# source_eagle.net
KiCad netlist of a schematic drawn in EAGLE
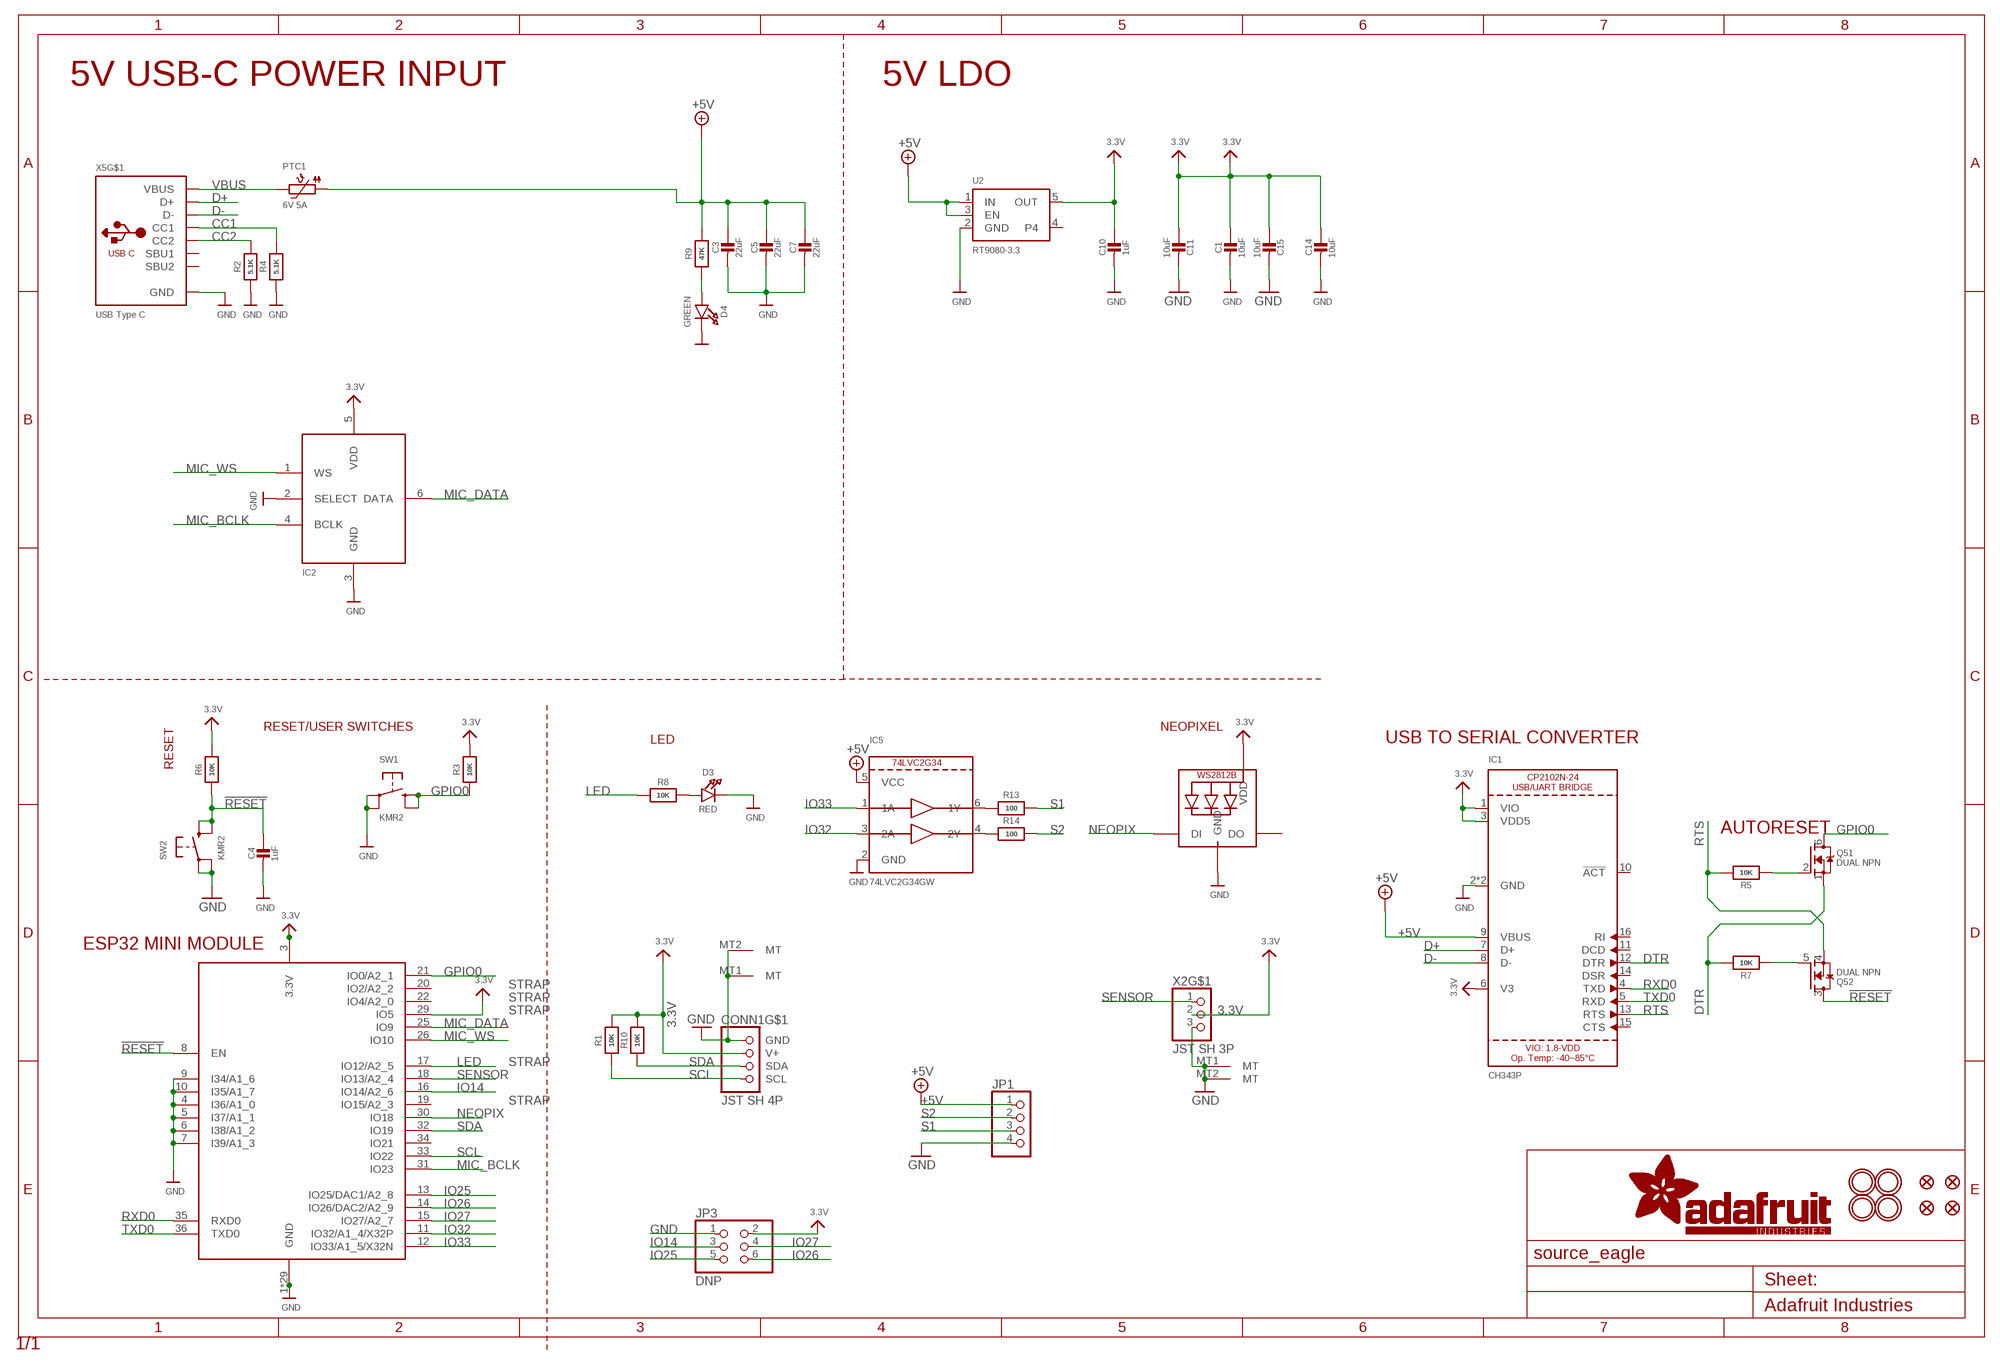
[diagram p0: schematic, sheet 1]

(export (version "E")
  (design (tool "Eeschema 10.0.6"))
  (components
    (comp (ref "C1")
      (value "10uF")
      (footprint "eagle-import:0805-NO")
      (libsource (lib "eagle-import") (part "CAP_CERAMIC0805-NOOUTLINE"))
    )
    (comp (ref "C3")
      (value "22uF")
      (footprint "eagle-import:0805-NO")
      (libsource (lib "eagle-import") (part "CAP_CERAMIC0805-NOOUTLINE"))
    )
    (comp (ref "C4")
      (value "1uF")
      (footprint "eagle-import:_0402NO")
      (libsource (lib "eagle-import") (part "CAP_CERAMIC_0402NO"))
    )
    (comp (ref "C5")
      (value "22uF")
      (footprint "eagle-import:0805-NO")
      (libsource (lib "eagle-import") (part "CAP_CERAMIC0805-NOOUTLINE"))
    )
    (comp (ref "C7")
      (value "22uF")
      (footprint "eagle-import:0805-NO")
      (libsource (lib "eagle-import") (part "CAP_CERAMIC0805-NOOUTLINE"))
    )
    (comp (ref "C10")
      (value "1uF")
      (footprint "eagle-import:_0402NO")
      (libsource (lib "eagle-import") (part "CAP_CERAMIC_0402NO"))
    )
    (comp (ref "C11")
      (value "10uF")
      (footprint "eagle-import:0805-NO")
      (libsource (lib "eagle-import") (part "CAP_CERAMIC0805-NOOUTLINE"))
    )
    (comp (ref "C14")
      (value "10uF")
      (footprint "eagle-import:0805-NO")
      (libsource (lib "eagle-import") (part "CAP_CERAMIC0805-NOOUTLINE"))
    )
    (comp (ref "C15")
      (value "10uF")
      (footprint "eagle-import:0805-NO")
      (libsource (lib "eagle-import") (part "CAP_CERAMIC0805-NOOUTLINE"))
    )
    (comp (ref "CONN1")
      (value "JST SH 4P")
      (footprint "eagle-import:JST_SH4")
      (libsource (lib "eagle-import") (part "STEMMA_I2C_QT"))
    )
    (comp (ref "D3")
      (value "RED")
      (footprint "eagle-import:CHIPLED_0603_NOOUTLINE")
      (libsource (lib "eagle-import") (part "LED0603_NOOUTLINE"))
    )
    (comp (ref "D4")
      (value "GREEN")
      (footprint "eagle-import:CHIPLED_0603_NOOUTLINE")
      (libsource (lib "eagle-import") (part "LED0603_NOOUTLINE"))
    )
    (comp (ref "IC1")
      (value "CH343P")
      (footprint "eagle-import:QFN16_3MM")
      (libsource (lib "eagle-import") (part "CH343P"))
    )
    (comp (ref "IC2")
      (value "ICS-43434")
      (footprint "eagle-import:SPH0645LM4H")
      (libsource (lib "eagle-import") (part "MIC_I2S_SPH0645"))
    )
    (comp (ref "IC5")
      (value "74LVC2G34GW")
      (footprint "eagle-import:SC70-6L")
      (libsource (lib "eagle-import") (part "74LVC2G34GW"))
    )
    (comp (ref "JP1")
      (value "HEADER-1X4")
      (footprint "eagle-import:1X04_OVAL")
      (libsource (lib "eagle-import") (part "HEADER-1X4"))
    )
    (comp (ref "JP3")
      (value "DNP")
      (footprint "eagle-import:2X03_ROUND_70MIL")
      (libsource (lib "eagle-import") (part "HEADER-2X3"))
    )
    (comp (ref "LED1")
      (value "WS2812B_SK6805_1515")
      (footprint "eagle-import:SK6805_1515")
      (libsource (lib "eagle-import") (part "WS2812B_SK6805_1515"))
    )
    (comp (ref "PTC1")
      (value "6V 5A")
      (footprint "eagle-import:PTC1210")
      (libsource (lib "eagle-import") (part "PTC1210"))
    )
    (comp (ref "Q5")
      (value "DUAL NPN")
      (footprint "eagle-import:SOT363")
      (fields (field (name "JLC_ROTATION") "90"))
      (libsource (lib "eagle-import") (part "MOSFET-N_DUAL"))
    )
    (comp (ref "R1")
      (value "10K")
      (footprint "eagle-import:_0402NO")
      (libsource (lib "eagle-import") (part "RESISTOR_0402NO"))
    )
    (comp (ref "R2")
      (value "5.1K")
      (footprint "eagle-import:_0402NO")
      (libsource (lib "eagle-import") (part "RESISTOR_0402NO"))
    )
    (comp (ref "R3")
      (value "10K")
      (footprint "eagle-import:_0402NO")
      (libsource (lib "eagle-import") (part "RESISTOR_0402NO"))
    )
    (comp (ref "R4")
      (value "5.1K")
      (footprint "eagle-import:_0402NO")
      (libsource (lib "eagle-import") (part "RESISTOR_0402NO"))
    )
    (comp (ref "R5")
      (value "10K")
      (footprint "eagle-import:_0402NO")
      (libsource (lib "eagle-import") (part "RESISTOR_0402NO"))
    )
    (comp (ref "R6")
      (value "10K")
      (footprint "eagle-import:_0402NO")
      (libsource (lib "eagle-import") (part "RESISTOR_0402NO"))
    )
    (comp (ref "R7")
      (value "10K")
      (footprint "eagle-import:_0402NO")
      (libsource (lib "eagle-import") (part "RESISTOR_0402NO"))
    )
    (comp (ref "R8")
      (value "10K")
      (footprint "eagle-import:_0402NO")
      (libsource (lib "eagle-import") (part "RESISTOR_0402NO"))
    )
    (comp (ref "R9")
      (value "47K")
      (footprint "eagle-import:_0402NO")
      (libsource (lib "eagle-import") (part "RESISTOR_0402NO"))
    )
    (comp (ref "R10")
      (value "10K")
      (footprint "eagle-import:_0402NO")
      (libsource (lib "eagle-import") (part "RESISTOR_0402NO"))
    )
    (comp (ref "R13")
      (value "100")
      (footprint "eagle-import:_0402NO")
      (libsource (lib "eagle-import") (part "RESISTOR_0402NO"))
    )
    (comp (ref "R14")
      (value "100")
      (footprint "eagle-import:_0402NO")
      (libsource (lib "eagle-import") (part "RESISTOR_0402NO"))
    )
    (comp (ref "SW1")
      (value "KMR2")
      (footprint "eagle-import:BTN_RKB2_4.6X2.8")
      (libsource (lib "eagle-import") (part "SWITCH_TACT_SMT_RKB2"))
    )
    (comp (ref "SW2")
      (value "KMR2")
      (footprint "eagle-import:BTN_RKB2_4.6X2.8")
      (libsource (lib "eagle-import") (part "SWITCH_TACT_SMT_RKB2"))
    )
    (comp (ref "U$14")
      (value "MOUNTINGHOLE2.5")
      (footprint "eagle-import:MOUNTINGHOLE_2.5_PLATED")
      (libsource (lib "eagle-import") (part "MOUNTINGHOLE2.5"))
    )
    (comp (ref "U$20")
      (value "MOUNTINGHOLE2.5")
      (footprint "eagle-import:MOUNTINGHOLE_2.5_PLATED")
      (libsource (lib "eagle-import") (part "MOUNTINGHOLE2.5"))
    )
    (comp (ref "U$23")
      (value "FIDUCIAL_0.5MM")
      (footprint "eagle-import:FIDUCIAL_0.5MM")
      (libsource (lib "eagle-import") (part "FIDUCIAL_0.5MM"))
    )
    (comp (ref "U$25")
      (value "FIDUCIAL_0.5MM")
      (footprint "eagle-import:FIDUCIAL_0.5MM")
      (libsource (lib "eagle-import") (part "FIDUCIAL_0.5MM"))
    )
    (comp (ref "U$28")
      (value "MOUNTINGHOLE2.5")
      (footprint "eagle-import:MOUNTINGHOLE_2.5_PLATED")
      (libsource (lib "eagle-import") (part "MOUNTINGHOLE2.5"))
    )
    (comp (ref "U$31")
      (value "MOUNTINGHOLE2.5")
      (footprint "eagle-import:MOUNTINGHOLE_2.5_PLATED")
      (libsource (lib "eagle-import") (part "MOUNTINGHOLE2.5"))
    )
    (comp (ref "U$34")
      (value "FIDUCIAL_0.5MM")
      (footprint "eagle-import:FIDUCIAL_0.5MM")
      (libsource (lib "eagle-import") (part "FIDUCIAL_0.5MM"))
    )
    (comp (ref "U$35")
      (value "FIDUCIAL_0.5MM")
      (footprint "eagle-import:FIDUCIAL_0.5MM")
      (libsource (lib "eagle-import") (part "FIDUCIAL_0.5MM"))
    )
    (comp (ref "U2")
      (value "RT9080-3.3")
      (footprint "eagle-import:SOT23-5")
      (fields (field (name "JLC_ROTATION") "0"))
      (libsource (lib "eagle-import") (part "VREG_SOT23-5"))
    )
    (comp (ref "X2")
      (value "JST SH 3P")
      (footprint "eagle-import:JST_SH3")
      (libsource (lib "eagle-import") (part "CON_JST_SH_3PINHORZ"))
    )
    (comp (ref "X4")
      (value "ESP32-MINI-1")
      (footprint "eagle-import:ESP32-MINI-1")
      (libsource (lib "eagle-import") (part "ESP32-MINI-1"))
    )
    (comp (ref "X5")
      (value "USB Type C")
      (footprint "eagle-import:USB_C_CUSB31-CFM2AX-01-X")
      (libsource (lib "eagle-import") (part "USB_C"))
    )
  )
  (nets
    (net (code "1") (name "+5V") (class "Default")
      (node (ref "C3") (pin "1") (pinfunction "1_1") (pintype "passive"))
      (node (ref "C5") (pin "1") (pinfunction "1_1") (pintype "passive"))
      (node (ref "C7") (pin "1") (pinfunction "1_1") (pintype "passive"))
      (node (ref "IC1") (pin "9") (pinfunction "VBUS_9") (pintype "power_in"))
      (node (ref "IC5") (pin "5") (pinfunction "VCC_5") (pintype "power_in"))
      (node (ref "JP1") (pin "1") (pinfunction "1_1") (pintype "passive"))
      (node (ref "PTC1") (pin "P$1") (pinfunction "1_P$1") (pintype "passive"))
      (node (ref "R9") (pin "2") (pinfunction "2_2") (pintype "passive"))
      (node (ref "U2") (pin "1") (pinfunction "IN_1") (pintype "power_in"))
      (node (ref "U2") (pin "3") (pinfunction "EN_3") (pintype "input"))
    )
    (net (code "2") (name "/CC1") (class "Default")
      (node (ref "R4") (pin "2") (pinfunction "2_2") (pintype "passive"))
      (node (ref "X5") (pin "A5") (pinfunction "CC1_A5") (pintype "bidirectional"))
    )
    (net (code "3") (name "/CC2") (class "Default")
      (node (ref "R2") (pin "2") (pinfunction "2_2") (pintype "passive"))
      (node (ref "X5") (pin "B5") (pinfunction "CC2_B5") (pintype "bidirectional"))
    )
    (net (code "4") (name "/D+") (class "Default")
      (node (ref "IC1") (pin "7") (pinfunction "D+_7") (pintype "bidirectional"))
      (node (ref "X5") (pin "A6") (pinfunction "D+_A6") (pintype "bidirectional"))
      (node (ref "X5") (pin "B6") (pinfunction "D+_B6") (pintype "bidirectional"))
    )
    (net (code "5") (name "/D-") (class "Default")
      (node (ref "IC1") (pin "8") (pinfunction "D-_8") (pintype "bidirectional"))
      (node (ref "X5") (pin "A7") (pinfunction "D-_A7") (pintype "bidirectional"))
      (node (ref "X5") (pin "B7") (pinfunction "D-_B7") (pintype "bidirectional"))
    )
    (net (code "6") (name "/DTR") (class "Default")
      (node (ref "IC1") (pin "12") (pinfunction "DTR_12") (pintype "output"))
      (node (ref "Q5") (pin "1") (pinfunction "S_1") (pintype "bidirectional"))
      (node (ref "R7") (pin "2") (pinfunction "2_2") (pintype "passive"))
    )
    (net (code "7") (name "/GPIO0") (class "Default")
      (node (ref "Q5") (pin "6") (pinfunction "D_6") (pintype "bidirectional"))
      (node (ref "R3") (pin "1") (pinfunction "1_1") (pintype "passive"))
      (node (ref "SW1") (pin "B") (pinfunction "S_B") (pintype "passive"))
      (node (ref "SW1") (pin "B'") (pinfunction "S1_B'") (pintype "passive"))
      (node (ref "X4") (pin "21") (pinfunction "IO0/A2_1_21") (pintype "bidirectional"))
    )
    (net (code "8") (name "/IO14") (class "Default")
      (node (ref "JP3") (pin "3") (pinfunction "3_3") (pintype "passive"))
      (node (ref "X4") (pin "16") (pinfunction "IO14/A2_6_16") (pintype "bidirectional"))
    )
    (net (code "9") (name "/IO25") (class "Default")
      (node (ref "JP3") (pin "5") (pinfunction "5_5") (pintype "passive"))
      (node (ref "X4") (pin "13") (pinfunction "IO25/DAC1/A2_8_13") (pintype "bidirectional"))
    )
    (net (code "10") (name "/IO26") (class "Default")
      (node (ref "JP3") (pin "6") (pinfunction "6_6") (pintype "passive"))
      (node (ref "X4") (pin "14") (pinfunction "IO26/DAC2/A2_9_14") (pintype "bidirectional"))
    )
    (net (code "11") (name "/IO27") (class "Default")
      (node (ref "JP3") (pin "4") (pinfunction "4_4") (pintype "passive"))
      (node (ref "X4") (pin "15") (pinfunction "IO27/A2_7_15") (pintype "bidirectional"))
    )
    (net (code "12") (name "/IO32") (class "Default")
      (node (ref "IC5") (pin "3") (pinfunction "2A_3") (pintype "input"))
      (node (ref "X4") (pin "11") (pinfunction "IO32/A1_4/X32P_11") (pintype "bidirectional"))
    )
    (net (code "13") (name "/IO33") (class "Default")
      (node (ref "IC5") (pin "1") (pinfunction "1A_1") (pintype "input"))
      (node (ref "X4") (pin "12") (pinfunction "IO33/A1_5/X32N_12") (pintype "bidirectional"))
    )
    (net (code "14") (name "/LED") (class "Default")
      (node (ref "R8") (pin "1") (pinfunction "1_1") (pintype "passive"))
      (node (ref "X4") (pin "17") (pinfunction "IO12/A2_5_17") (pintype "bidirectional"))
    )
    (net (code "15") (name "/MIC_BCLK") (class "Default")
      (node (ref "IC2") (pin "4") (pinfunction "BCLK_4") (pintype "input"))
      (node (ref "X4") (pin "31") (pinfunction "IO23_31") (pintype "bidirectional"))
    )
    (net (code "16") (name "/MIC_DATA") (class "Default")
      (node (ref "IC2") (pin "6") (pinfunction "DATA_6") (pintype "output"))
      (node (ref "X4") (pin "25") (pinfunction "IO9_25") (pintype "bidirectional"))
    )
    (net (code "17") (name "/MIC_WS") (class "Default")
      (node (ref "IC2") (pin "1") (pinfunction "WS_1") (pintype "input"))
      (node (ref "X4") (pin "26") (pinfunction "IO10_26") (pintype "bidirectional"))
    )
    (net (code "18") (name "/NEOPIX") (class "Default")
      (node (ref "LED1") (pin "1") (pinfunction "DI_1") (pintype "input"))
      (node (ref "X4") (pin "30") (pinfunction "IO18_30") (pintype "bidirectional"))
    )
    (net (code "19") (name "/RTS") (class "Default")
      (node (ref "IC1") (pin "13") (pinfunction "RTS_13") (pintype "output"))
      (node (ref "Q5") (pin "4") (pinfunction "S_4") (pintype "bidirectional"))
      (node (ref "R5") (pin "2") (pinfunction "2_2") (pintype "passive"))
    )
    (net (code "20") (name "/RXD0") (class "Default")
      (node (ref "IC1") (pin "4") (pinfunction "TXD_4") (pintype "output"))
      (node (ref "X4") (pin "35") (pinfunction "RXD0_35") (pintype "input"))
    )
    (net (code "21") (name "/S1") (class "Default")
      (node (ref "JP1") (pin "3") (pinfunction "3_3") (pintype "passive"))
      (node (ref "R13") (pin "2") (pinfunction "2_2") (pintype "passive"))
    )
    (net (code "22") (name "/S2") (class "Default")
      (node (ref "JP1") (pin "2") (pinfunction "2_2") (pintype "passive"))
      (node (ref "R14") (pin "2") (pinfunction "2_2") (pintype "passive"))
    )
    (net (code "23") (name "/SCL") (class "Default")
      (node (ref "CONN1") (pin "4") (pinfunction "SCL_4") (pintype "passive"))
      (node (ref "R1") (pin "1") (pinfunction "1_1") (pintype "passive"))
      (node (ref "X4") (pin "33") (pinfunction "IO22_33") (pintype "bidirectional"))
    )
    (net (code "24") (name "/SDA") (class "Default")
      (node (ref "CONN1") (pin "3") (pinfunction "SDA_3") (pintype "passive"))
      (node (ref "R10") (pin "1") (pinfunction "1_1") (pintype "passive"))
      (node (ref "X4") (pin "32") (pinfunction "IO19_32") (pintype "bidirectional"))
    )
    (net (code "25") (name "/SENSOR") (class "Default")
      (node (ref "X2") (pin "1") (pinfunction "1_1") (pintype "passive"))
      (node (ref "X4") (pin "18") (pinfunction "IO13/A2_4_18") (pintype "bidirectional"))
    )
    (net (code "26") (name "/TXD0") (class "Default")
      (node (ref "IC1") (pin "5") (pinfunction "RXD_5") (pintype "input"))
      (node (ref "X4") (pin "36") (pinfunction "TXD0_36") (pintype "output"))
    )
    (net (code "27") (name "/VBUS") (class "Default")
      (node (ref "PTC1") (pin "P$2") (pinfunction "2_P$2") (pintype "passive"))
      (node (ref "X5") (pin "A4B9") (pinfunction "VBUS_A4B9") (pintype "power_in"))
      (node (ref "X5") (pin "B4A9") (pinfunction "VBUS_B4A9") (pintype "power_in"))
    )
    (net (code "28") (name "/~{RESET}") (class "Default")
      (node (ref "C4") (pin "1") (pinfunction "1_1") (pintype "passive"))
      (node (ref "Q5") (pin "3") (pinfunction "D_3") (pintype "bidirectional"))
      (node (ref "R6") (pin "1") (pinfunction "1_1") (pintype "passive"))
      (node (ref "SW2") (pin "B") (pinfunction "S_B") (pintype "passive"))
      (node (ref "SW2") (pin "B'") (pinfunction "S1_B'") (pintype "passive"))
      (node (ref "X4") (pin "8") (pinfunction "EN_8") (pintype "input"))
    )
    (net (code "29") (name "3.3V") (class "Default")
      (node (ref "C1") (pin "1") (pinfunction "1_1") (pintype "passive"))
      (node (ref "C10") (pin "1") (pinfunction "1_1") (pintype "passive"))
      (node (ref "C11") (pin "1") (pinfunction "1_1") (pintype "passive"))
      (node (ref "C14") (pin "1") (pinfunction "1_1") (pintype "passive"))
      (node (ref "C15") (pin "1") (pinfunction "1_1") (pintype "passive"))
      (node (ref "CONN1") (pin "2") (pinfunction "V+_2") (pintype "passive"))
      (node (ref "IC1") (pin "1") (pinfunction "VIO_1") (pintype "power_in"))
      (node (ref "IC1") (pin "3") (pinfunction "VDD5_3") (pintype "power_in"))
      (node (ref "IC1") (pin "6") (pinfunction "V3_6") (pintype "passive"))
      (node (ref "IC2") (pin "5") (pinfunction "VDD_5") (pintype "power_in"))
      (node (ref "JP3") (pin "2") (pinfunction "2_2") (pintype "passive"))
      (node (ref "LED1") (pin "2") (pinfunction "VDD_2") (pintype "power_in"))
      (node (ref "R1") (pin "2") (pinfunction "2_2") (pintype "passive"))
      (node (ref "R10") (pin "2") (pinfunction "2_2") (pintype "passive"))
      (node (ref "R3") (pin "2") (pinfunction "2_2") (pintype "passive"))
      (node (ref "R6") (pin "2") (pinfunction "2_2") (pintype "passive"))
      (node (ref "U2") (pin "5") (pinfunction "OUT_5") (pintype "power_in"))
      (node (ref "X2") (pin "2") (pinfunction "2_2") (pintype "passive"))
      (node (ref "X4") (pin "29") (pinfunction "IO5_29") (pintype "bidirectional"))
      (node (ref "X4") (pin "3") (pinfunction "3.3V_3") (pintype "passive"))
    )
    (net (code "30") (name "GND") (class "Default")
      (node (ref "C1") (pin "2") (pinfunction "2_2") (pintype "passive"))
      (node (ref "C10") (pin "2") (pinfunction "2_2") (pintype "passive"))
      (node (ref "C11") (pin "2") (pinfunction "2_2") (pintype "passive"))
      (node (ref "C14") (pin "2") (pinfunction "2_2") (pintype "passive"))
      (node (ref "C15") (pin "2") (pinfunction "2_2") (pintype "passive"))
      (node (ref "C3") (pin "2") (pinfunction "2_2") (pintype "passive"))
      (node (ref "C4") (pin "2") (pinfunction "2_2") (pintype "passive"))
      (node (ref "C5") (pin "2") (pinfunction "2_2") (pintype "passive"))
      (node (ref "C7") (pin "2") (pinfunction "2_2") (pintype "passive"))
      (node (ref "CONN1") (pin "1") (pinfunction "GND_1") (pintype "passive"))
      (node (ref "CONN1") (pin "MT1") (pinfunction "MT_MT1") (pintype "bidirectional"))
      (node (ref "CONN1") (pin "MT2") (pinfunction "MT_MT2") (pintype "bidirectional"))
      (node (ref "D3") (pin "C") (pinfunction "C_C") (pintype "passive"))
      (node (ref "D4") (pin "C") (pinfunction "C_C") (pintype "passive"))
      (node (ref "IC1") (pin "2") (pinfunction "GND_2") (pintype "power_in"))
      (node (ref "IC1") (pin "THERMAL") (pinfunction "GND_THERMAL") (pintype "power_in"))
      (node (ref "IC2") (pin "2") (pinfunction "SELECT_2") (pintype "input"))
      (node (ref "IC2") (pin "3") (pinfunction "GND_3") (pintype "power_in"))
      (node (ref "IC5") (pin "2") (pinfunction "GND_2") (pintype "power_in"))
      (node (ref "JP1") (pin "4") (pinfunction "4_4") (pintype "passive"))
      (node (ref "JP3") (pin "1") (pinfunction "1_1") (pintype "passive"))
      (node (ref "LED1") (pin "4") (pinfunction "GND_4") (pintype "power_in"))
      (node (ref "R2") (pin "1") (pinfunction "1_1") (pintype "passive"))
      (node (ref "R4") (pin "1") (pinfunction "1_1") (pintype "passive"))
      (node (ref "SW1") (pin "A") (pinfunction "P_A") (pintype "passive"))
      (node (ref "SW1") (pin "A'") (pinfunction "P1_A'") (pintype "passive"))
      (node (ref "SW2") (pin "A") (pinfunction "P_A") (pintype "passive"))
      (node (ref "SW2") (pin "A'") (pinfunction "P1_A'") (pintype "passive"))
      (node (ref "U2") (pin "2") (pinfunction "GND_2") (pintype "power_in"))
      (node (ref "X2") (pin "3") (pinfunction "3_3") (pintype "passive"))
      (node (ref "X2") (pin "MT1") (pinfunction "MT_MT1") (pintype "bidirectional"))
      (node (ref "X2") (pin "MT2") (pinfunction "MT_MT2") (pintype "bidirectional"))
      (node (ref "X4") (pin "1") (pinfunction "GND_1") (pintype "passive"))
      (node (ref "X4") (pin "10") (pinfunction "I35/A1_7_10") (pintype "input"))
      (node (ref "X4") (pin "2") (pinfunction "GND_2") (pintype "passive"))
      (node (ref "X4") (pin "27") (pinfunction "GND_27") (pintype "passive"))
      (node (ref "X4") (pin "38") (pinfunction "GND_38") (pintype "passive"))
      (node (ref "X4") (pin "39") (pinfunction "GND_39") (pintype "passive"))
      (node (ref "X4") (pin "4") (pinfunction "I36/A1_0_4") (pintype "input"))
      (node (ref "X4") (pin "40") (pinfunction "GND_40") (pintype "passive"))
      (node (ref "X4") (pin "41") (pinfunction "GND_41") (pintype "passive"))
      (node (ref "X4") (pin "42") (pinfunction "GND_42") (pintype "passive"))
      (node (ref "X4") (pin "43") (pinfunction "GND_43") (pintype "passive"))
      (node (ref "X4") (pin "44") (pinfunction "GND_44") (pintype "passive"))
      (node (ref "X4") (pin "45") (pinfunction "GND_45") (pintype "passive"))
      (node (ref "X4") (pin "46") (pinfunction "GND_46") (pintype "passive"))
      (node (ref "X4") (pin "47") (pinfunction "GND_47") (pintype "passive"))
      (node (ref "X4") (pin "48") (pinfunction "GND_48") (pintype "passive"))
      (node (ref "X4") (pin "49") (pinfunction "GND_49") (pintype "passive"))
      (node (ref "X4") (pin "5") (pinfunction "I37/A1_1_5") (pintype "input"))
      (node (ref "X4") (pin "50") (pinfunction "GND_50") (pintype "passive"))
      (node (ref "X4") (pin "51") (pinfunction "GND_51") (pintype "passive"))
      (node (ref "X4") (pin "52") (pinfunction "GND_52") (pintype "passive"))
      (node (ref "X4") (pin "53") (pinfunction "GND_53") (pintype "passive"))
      (node (ref "X4") (pin "54") (pinfunction "GND_54") (pintype "passive"))
      (node (ref "X4") (pin "55") (pinfunction "GND_55") (pintype "passive"))
      (node (ref "X4") (pin "56") (pinfunction "GND_56") (pintype "passive"))
      (node (ref "X4") (pin "57") (pinfunction "GND_57") (pintype "passive"))
      (node (ref "X4") (pin "58") (pinfunction "GND_58") (pintype "passive"))
      (node (ref "X4") (pin "59") (pinfunction "GND_59") (pintype "passive"))
      (node (ref "X4") (pin "6") (pinfunction "I38/A1_2_6") (pintype "input"))
      (node (ref "X4") (pin "60") (pinfunction "GND_60") (pintype "passive"))
      (node (ref "X4") (pin "61") (pinfunction "GND_61") (pintype "passive"))
      (node (ref "X4") (pin "62") (pinfunction "GND_62") (pintype "passive"))
      (node (ref "X4") (pin "63") (pinfunction "GND_63") (pintype "passive"))
      (node (ref "X4") (pin "7") (pinfunction "I39/A1_3_7") (pintype "input"))
      (node (ref "X4") (pin "9") (pinfunction "I34/A1_6_9") (pintype "input"))
      (node (ref "X5") (pin "A1B12") (pinfunction "GND_A1B12") (pintype "power_in"))
      (node (ref "X5") (pin "B1A12") (pinfunction "GND_B1A12") (pintype "power_in"))
    )
    (net (code "31") (name "Net-(D3-PadA)") (class "Default")
      (node (ref "D3") (pin "A") (pinfunction "A_A") (pintype "passive"))
      (node (ref "R8") (pin "2") (pinfunction "2_2") (pintype "passive"))
    )
    (net (code "32") (name "Net-(D4-PadA)") (class "Default")
      (node (ref "D4") (pin "A") (pinfunction "A_A") (pintype "passive"))
      (node (ref "R9") (pin "1") (pinfunction "1_1") (pintype "passive"))
    )
    (net (code "33") (name "Net-(IC5-1Y)") (class "Default")
      (node (ref "IC5") (pin "6") (pinfunction "1Y_6") (pintype "output"))
      (node (ref "R13") (pin "1") (pinfunction "1_1") (pintype "passive"))
    )
    (net (code "34") (name "Net-(IC5-2Y)") (class "Default")
      (node (ref "IC5") (pin "4") (pinfunction "2Y_4") (pintype "output"))
      (node (ref "R14") (pin "1") (pinfunction "1_1") (pintype "passive"))
    )
    (net (code "35") (name "Net-(Q5A-G)") (class "Default")
      (node (ref "Q5") (pin "2") (pinfunction "G_2") (pintype "bidirectional"))
      (node (ref "R5") (pin "1") (pinfunction "1_1") (pintype "passive"))
    )
    (net (code "36") (name "Net-(Q5B-G)") (class "Default")
      (node (ref "Q5") (pin "5") (pinfunction "G_5") (pintype "bidirectional"))
      (node (ref "R7") (pin "1") (pinfunction "1_1") (pintype "passive"))
    )
    (net (code "37") (name "unconnected-(IC1-CTS-Pad15)") (class "Default")
      (node (ref "IC1") (pin "15") (pinfunction "CTS_15") (pintype "input"))
    )
    (net (code "38") (name "unconnected-(IC1-DCD-Pad11)") (class "Default")
      (node (ref "IC1") (pin "11") (pinfunction "DCD_11") (pintype "input"))
    )
    (net (code "39") (name "unconnected-(IC1-DSR-Pad14)") (class "Default")
      (node (ref "IC1") (pin "14") (pinfunction "DSR_14") (pintype "input"))
    )
    (net (code "40") (name "unconnected-(IC1-RI-Pad16)") (class "Default")
      (node (ref "IC1") (pin "16") (pinfunction "RI_16") (pintype "input"))
    )
    (net (code "41") (name "unconnected-(IC1-~{ACT}-Pad10)") (class "Default")
      (node (ref "IC1") (pin "10") (pinfunction "~{ACT}_10") (pintype "bidirectional"))
    )
    (net (code "42") (name "unconnected-(LED1-DO-Pad3)") (class "Default")
      (node (ref "LED1") (pin "3") (pinfunction "DO_3") (pintype "output"))
    )
    (net (code "43") (name "unconnected-(U2-P4-Pad4)") (class "Default")
      (node (ref "U2") (pin "4") (pinfunction "P4_4") (pintype "bidirectional"))
    )
    (net (code "44") (name "unconnected-(X4-IO2{slash}A2_2-Pad20)") (class "Default")
      (node (ref "X4") (pin "20") (pinfunction "IO2/A2_2_20") (pintype "bidirectional"))
    )
    (net (code "45") (name "unconnected-(X4-IO4{slash}A2_0-Pad22)") (class "Default")
      (node (ref "X4") (pin "22") (pinfunction "IO4/A2_0_22") (pintype "bidirectional"))
    )
    (net (code "46") (name "unconnected-(X4-IO15{slash}A2_3-Pad19)") (class "Default")
      (node (ref "X4") (pin "19") (pinfunction "IO15/A2_3_19") (pintype "bidirectional"))
    )
    (net (code "47") (name "unconnected-(X4-IO21-Pad34)") (class "Default")
      (node (ref "X4") (pin "34") (pinfunction "IO21_34") (pintype "bidirectional"))
    )
    (net (code "48") (name "unconnected-(X5A-SBU1-PadA8)") (class "Default")
      (node (ref "X5") (pin "A8") (pinfunction "SBU1_A8") (pintype "bidirectional"))
    )
    (net (code "49") (name "unconnected-(X5A-SBU2-PadB8)") (class "Default")
      (node (ref "X5") (pin "B8") (pinfunction "SBU2_B8") (pintype "bidirectional"))
    )
  )
)
